# main.net
KiCad netlist of a schematic drawn in EAGLE
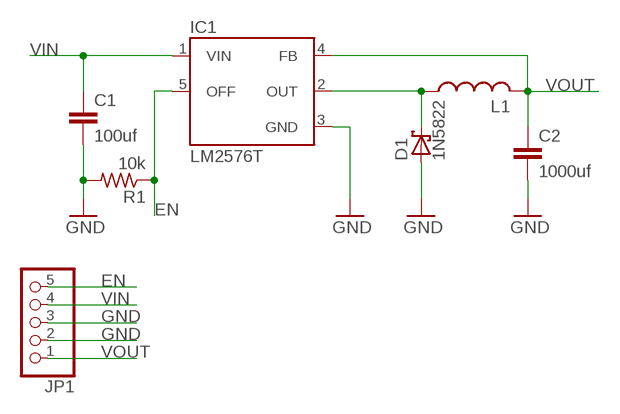
[diagram p0: schematic, sheet 1]

(export (version "E")
  (design (tool "Eeschema 10.0.6"))
  (components
    (comp (ref "C1")
      (value "100uf")
      (footprint "eagle-import:C050-075X075")
      (libsource (lib "eagle-import") (part "C-EU050-075X075"))
    )
    (comp (ref "C2")
      (value "1000uf")
      (footprint "eagle-import:C050-075X075")
      (libsource (lib "eagle-import") (part "C-EU050-075X075"))
    )
    (comp (ref "D1")
      (value "1N5822")
      (footprint "eagle-import:CB417-15")
      (libsource (lib "eagle-import") (part "SCHOTTKY-DIODECB417-15"))
    )
    (comp (ref "IC1")
      (value "LM2576T")
      (footprint "eagle-import:TO220-5")
      (libsource (lib "eagle-import") (part "LM2576T"))
    )
    (comp (ref "JP1")
      (value "PINHD-1X5/90")
      (footprint "eagle-import:1X05_90")
      (libsource (lib "eagle-import") (part "PINHD-1X5/90"))
    )
    (comp (ref "L1")
      (value "L-USTJ3-U1")
      (footprint "eagle-import:TJ3-U1")
      (libsource (lib "eagle-import") (part "L-USTJ3-U1"))
    )
    (comp (ref "R1")
      (value "10k")
      (footprint "eagle-import:0207_7")
      (libsource (lib "eagle-import") (part "R-US_0207/7"))
    )
  )
  (nets
    (net (code "1") (name "/EN") (class "Default")
      (node (ref "IC1") (pin "5") (pinfunction "OFF_5") (pintype "input"))
      (node (ref "JP1") (pin "5") (pinfunction "5_5") (pintype "passive"))
      (node (ref "R1") (pin "1") (pinfunction "1_1") (pintype "passive"))
    )
    (net (code "2") (name "/VIN") (class "Default")
      (node (ref "C1") (pin "1") (pinfunction "1_1") (pintype "passive"))
      (node (ref "IC1") (pin "1") (pinfunction "VIN_1") (pintype "power_in"))
      (node (ref "JP1") (pin "4") (pinfunction "4_4") (pintype "passive"))
    )
    (net (code "3") (name "/VOUT") (class "Default")
      (node (ref "C2") (pin "1") (pinfunction "1_1") (pintype "passive"))
      (node (ref "IC1") (pin "4") (pinfunction "FB_4") (pintype "input"))
      (node (ref "JP1") (pin "1") (pinfunction "1_1") (pintype "passive"))
      (node (ref "L1") (pin "2") (pinfunction "2_2") (pintype "passive"))
    )
    (net (code "4") (name "GND") (class "Default")
      (node (ref "C1") (pin "2") (pinfunction "2_2") (pintype "passive"))
      (node (ref "C2") (pin "2") (pinfunction "2_2") (pintype "passive"))
      (node (ref "D1") (pin "A") (pinfunction "A_A") (pintype "passive"))
      (node (ref "IC1") (pin "3") (pinfunction "GND_3") (pintype "power_in"))
      (node (ref "JP1") (pin "2") (pinfunction "2_2") (pintype "passive"))
      (node (ref "JP1") (pin "3") (pinfunction "3_3") (pintype "passive"))
      (node (ref "R1") (pin "2") (pinfunction "2_2") (pintype "passive"))
    )
    (net (code "5") (name "Net-(IC1-OUT)") (class "Default")
      (node (ref "D1") (pin "C") (pinfunction "C_C") (pintype "passive"))
      (node (ref "IC1") (pin "2") (pinfunction "OUT_2") (pintype "output"))
      (node (ref "L1") (pin "1") (pinfunction "1_1") (pintype "passive"))
    )
  )
)
